# COMS0002_AFSK.net
KiCad netlist of a schematic drawn in Altium Designer
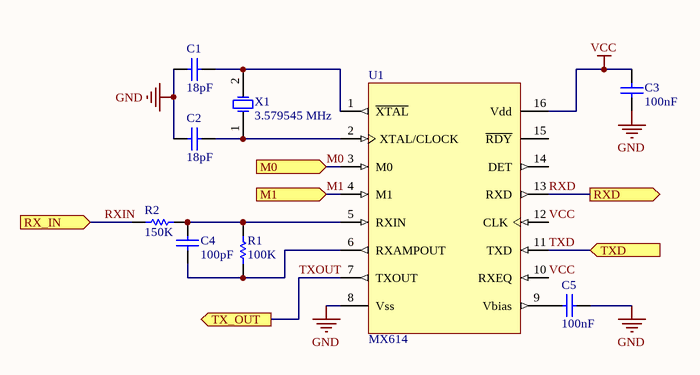
[diagram p0: COMS0002_AFSK.SchDoc]

(export (version "E")
  (design (tool "Eeschema 10.0.6"))
  (components
    (comp (ref "C1")
      (value "18pF")
      (footprint "CAPC2012M")
      (description "Capacitor")
      (fields (field (name "Comment") "Cap") (field (name "PUBLISHER") "Altium Limited"))
      (libsource (lib "Miscellaneous Devices") (part "Cap"))
    )
    (comp (ref "C2")
      (value "18pF")
      (footprint "CAPC2012M")
      (description "Capacitor")
      (fields (field (name "Comment") "Cap") (field (name "PUBLISHER") "Altium Limited"))
      (libsource (lib "Miscellaneous Devices") (part "Cap"))
    )
    (comp (ref "C3")
      (value "100nF")
      (footprint "CAPC2012M")
      (description "Capacitor")
      (fields (field (name "Comment") "Cap") (field (name "PUBLISHER") "Altium Limited"))
      (libsource (lib "Miscellaneous Devices") (part "Cap"))
    )
    (comp (ref "C4")
      (value "100pF")
      (footprint "CAPC2012M")
      (description "Capacitor")
      (fields (field (name "Comment") "Cap") (field (name "PUBLISHER") "Altium Limited"))
      (libsource (lib "Miscellaneous Devices") (part "Cap"))
    )
    (comp (ref "C5")
      (value "100nF")
      (footprint "CAPC2012M")
      (description "Capacitor")
      (fields (field (name "Comment") "Cap") (field (name "PUBLISHER") "Altium Limited"))
      (libsource (lib "Miscellaneous Devices") (part "Cap"))
    )
    (comp (ref "R1")
      (value "100K")
      (footprint "RESC2012M")
      (description "Resistor")
      (fields (field (name "Comment") "Res1") (field (name "PUBLISHER") "Altium Limited"))
      (libsource (lib "Miscellaneous Devices") (part "Res1"))
    )
    (comp (ref "R2")
      (value "150K")
      (footprint "RESC2012M")
      (description "Resistor")
      (fields (field (name "Comment") "Res1") (field (name "PUBLISHER") "Altium Limited"))
      (libsource (lib "Miscellaneous Devices") (part "Res1"))
    )
    (comp (ref "U1")
      (value "MX614")
      (footprint "SOIC127P1030X270-16N")
      (description "Bell 202 Compatible Modem")
      (fields (field (name "PUBLISHER") "Altium Limited"))
      (libsource (lib "MX614") (part "MX614"))
    )
    (comp (ref "X1")
      (value "3.579545 MHz")
      (footprint "CSM-7")
      (description "Crystal Oscillator")
      (fields (field (name "PUBLISHER") "Altium Limited"))
      (libsource (lib "ECS Crystal Oscillator") (part "ECS-110-S-5P"))
    )
  )
  (nets
    (net (code "1") (name "/M0") (class "Default")
      (node (ref "U1") (pin "3") (pinfunction "M0_3") (pintype "input"))
    )
    (net (code "2") (name "/M1") (class "Default")
      (node (ref "U1") (pin "4") (pinfunction "M1_4") (pintype "input"))
    )
    (net (code "3") (name "/RXD") (class "Default")
      (node (ref "U1") (pin "13") (pinfunction "RXD_13") (pintype "output"))
    )
    (net (code "4") (name "/RXIN") (class "Default")
      (node (ref "R2") (pin "1") (pinfunction "1_1") (pintype "passive"))
    )
    (net (code "5") (name "/TXD") (class "Default")
      (node (ref "U1") (pin "11") (pinfunction "TXD_11") (pintype "input"))
    )
    (net (code "6") (name "/TXOUT") (class "Default")
      (node (ref "U1") (pin "7") (pinfunction "TXOUT_7") (pintype "output"))
    )
    (net (code "7") (name "GND") (class "Default")
      (node (ref "C1") (pin "1") (pinfunction "1_1") (pintype "passive"))
      (node (ref "C2") (pin "1") (pinfunction "1_1") (pintype "passive"))
      (node (ref "C3") (pin "2") (pinfunction "2_2") (pintype "passive"))
      (node (ref "C5") (pin "1") (pinfunction "1_1") (pintype "passive"))
      (node (ref "U1") (pin "8") (pinfunction "Vss_8") (pintype "power_in"))
    )
    (net (code "8") (name "Net-(U1-RXAMPOUT)") (class "Default")
      (node (ref "C4") (pin "1") (pinfunction "1_1") (pintype "passive"))
      (node (ref "R1") (pin "1") (pinfunction "1_1") (pintype "passive"))
      (node (ref "U1") (pin "6") (pinfunction "RXAMPOUT_6") (pintype "output"))
    )
    (net (code "9") (name "Net-(U1-RXIN)") (class "Default")
      (node (ref "C4") (pin "2") (pinfunction "2_2") (pintype "passive"))
      (node (ref "R1") (pin "2") (pinfunction "2_2") (pintype "passive"))
      (node (ref "R2") (pin "2") (pinfunction "2_2") (pintype "passive"))
      (node (ref "U1") (pin "5") (pinfunction "RXIN_5") (pintype "input"))
    )
    (net (code "10") (name "Net-(U1-Vbias)") (class "Default")
      (node (ref "C5") (pin "2") (pinfunction "2_2") (pintype "passive"))
      (node (ref "U1") (pin "9") (pinfunction "Vbias_9") (pintype "output"))
    )
    (net (code "11") (name "Net-(U1-XTAL{slash}CLOCK)") (class "Default")
      (node (ref "C2") (pin "2") (pinfunction "2_2") (pintype "passive"))
      (node (ref "U1") (pin "2") (pinfunction "XTAL/CLOCK_2") (pintype "input"))
      (node (ref "X1") (pin "1") (pinfunction "OSC1_1") (pintype "passive"))
    )
    (net (code "12") (name "Net-(U1-~{XTAL})") (class "Default")
      (node (ref "C1") (pin "2") (pinfunction "2_2") (pintype "passive"))
      (node (ref "U1") (pin "1") (pinfunction "~{XTAL}_1") (pintype "output"))
      (node (ref "X1") (pin "2") (pinfunction "OSC2_2") (pintype "passive"))
    )
    (net (code "13") (name "VCC") (class "Default")
      (node (ref "C3") (pin "1") (pinfunction "1_1") (pintype "passive"))
      (node (ref "U1") (pin "10") (pinfunction "RXEQ_10") (pintype "input"))
      (node (ref "U1") (pin "12") (pinfunction "CLK_12") (pintype "input"))
      (node (ref "U1") (pin "16") (pinfunction "Vdd_16") (pintype "power_in"))
    )
    (net (code "14") (name "unconnected-(U1-DET-Pad14)") (class "Default")
      (node (ref "U1") (pin "14") (pinfunction "DET_14") (pintype "output"))
    )
    (net (code "15") (name "unconnected-(U1-~{RDY}-Pad15)") (class "Default")
      (node (ref "U1") (pin "15") (pinfunction "~{RDY}_15") (pintype "passive"))
    )
  )
)
